# LPCB218_-_CORE_INTERFACE.net
KiCad netlist of a schematic drawn in Altium Designer
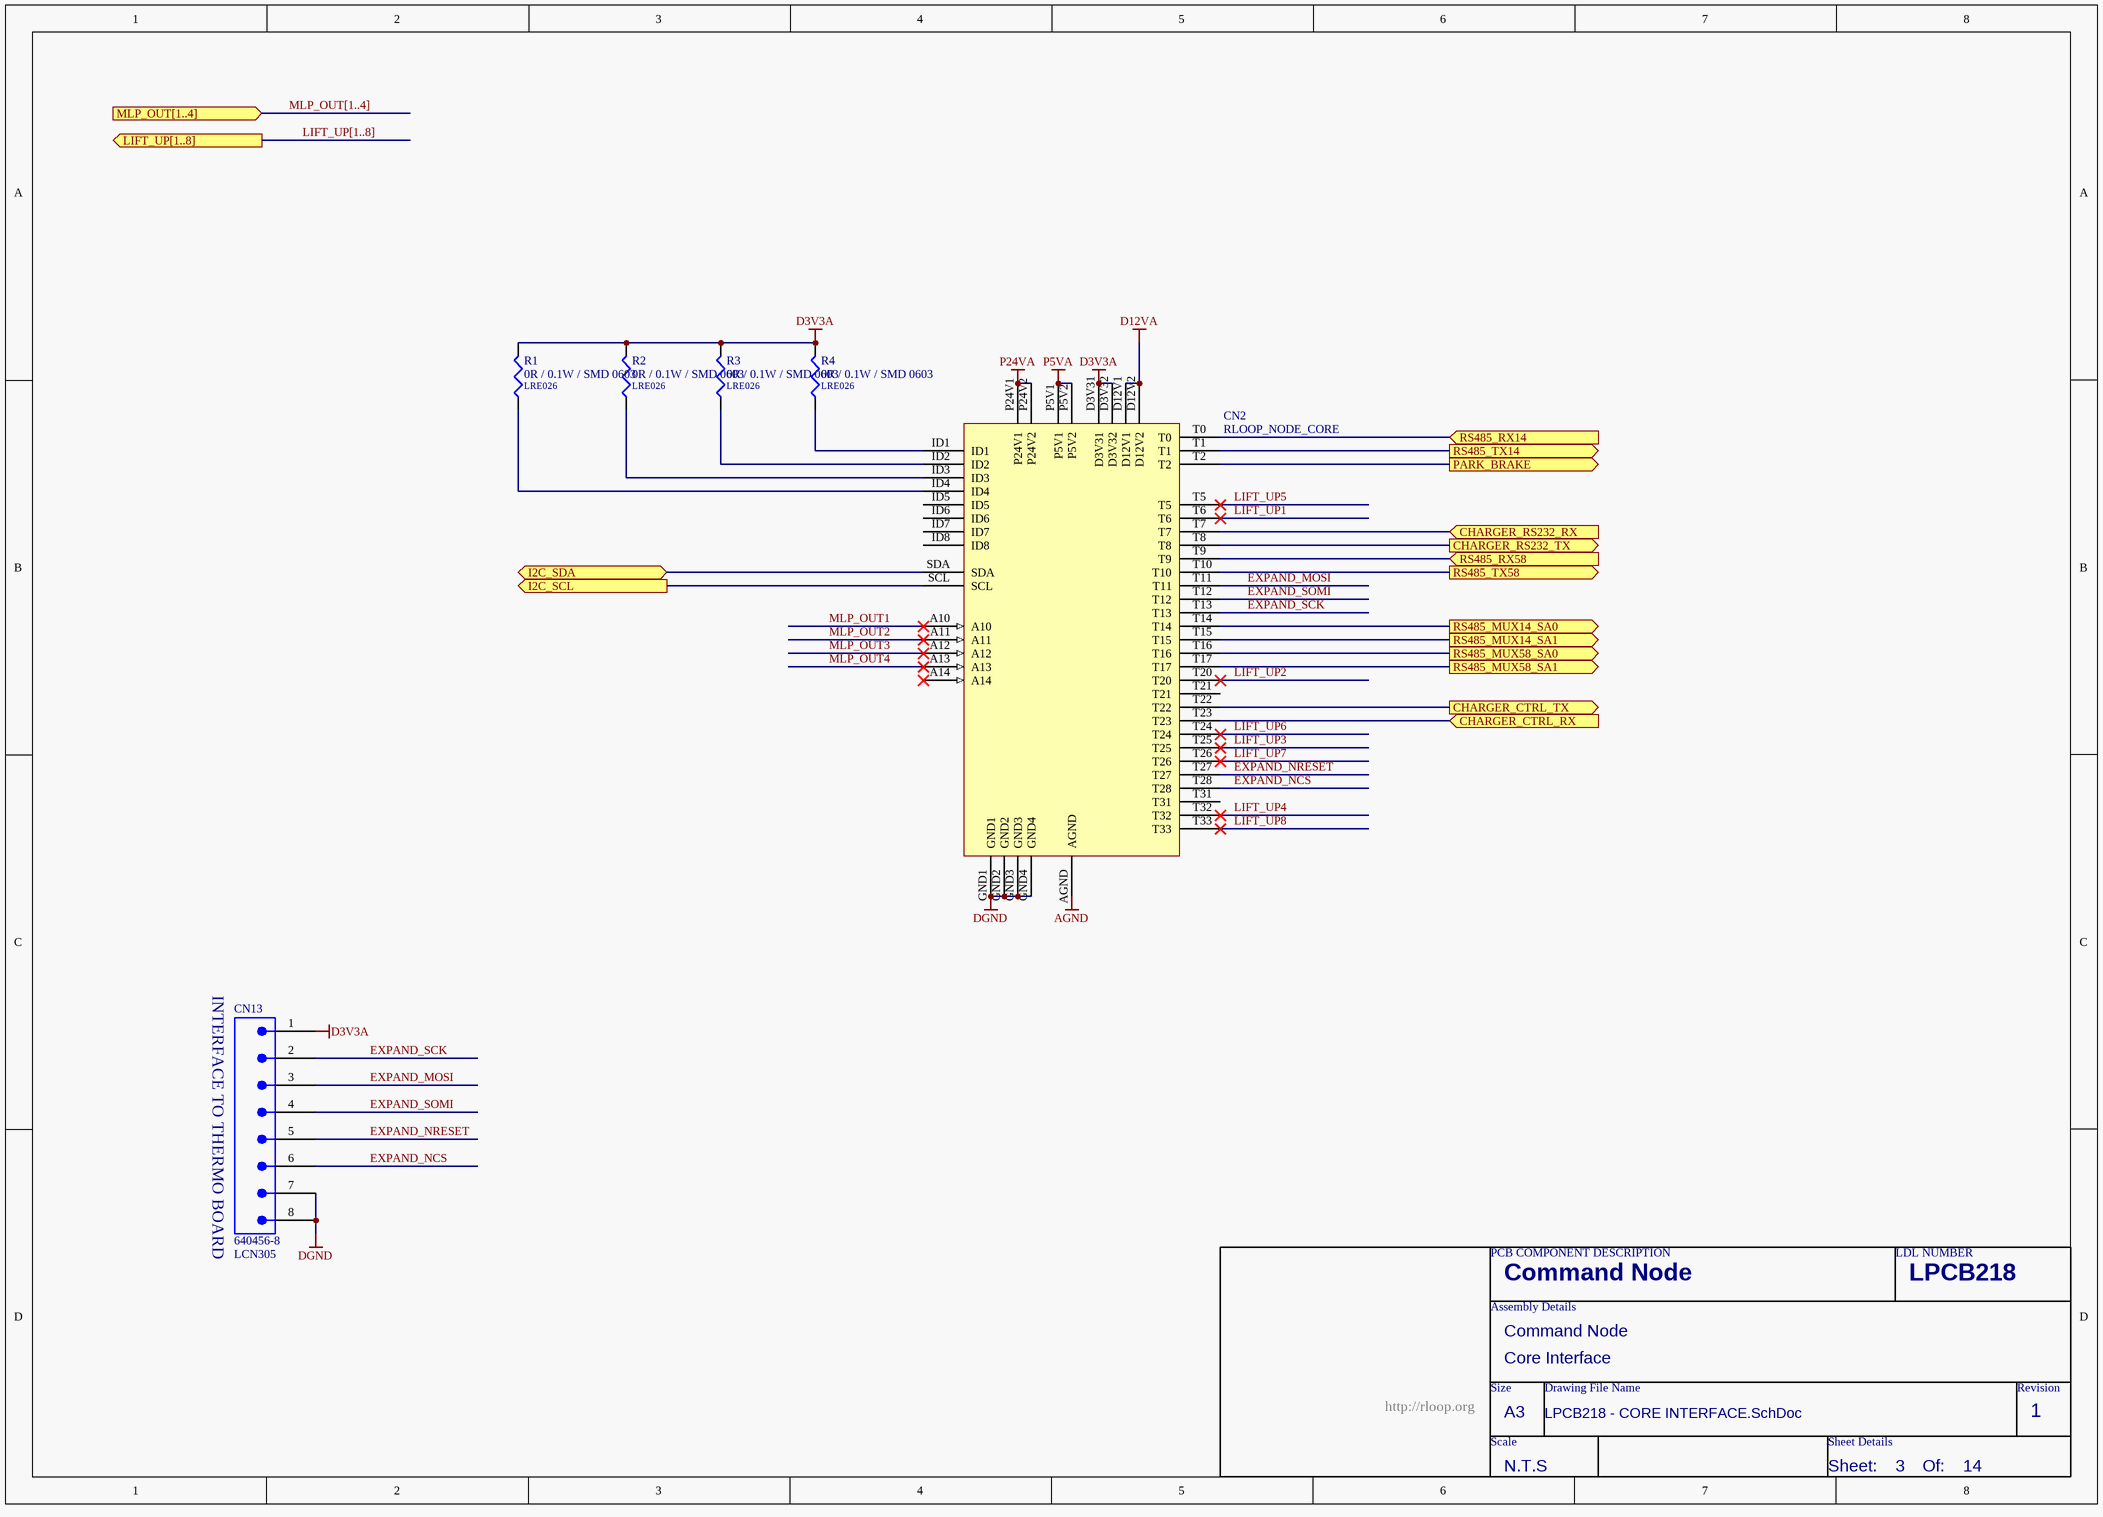
[diagram p0: LPCB218 - CORE INTERFACE.SchDoc]

(export (version "E")
  (design (tool "Eeschema 10.0.6"))
  (components
    (comp (ref "CN2")
      (value "RLOOP_NODE_CORE")
      (footprint "RLOOP_NODE_CORE")
      (description "rLoop Node Core Connector")
      (libsource (lib "LDL_Connectors") (part "RLOOP_NODE_CORE"))
    )
    (comp (ref "CN13")
      (value "640456-8")
      (footprint "640456-8")
      (description "Connector, Male Header, 8 Way")
      (fields (field (name "LDL_NUMBER") "LCN305"))
      (libsource (lib "LDL_Connectors") (part "640456-8"))
    )
    (comp (ref "R1")
      (value "0R / 0.1W / SMD 0603")
      (footprint "LFP020__CR1608-0603-IPC7351_B")
      (description "Resistor, Ceramic Chip, 0R, 0.1W, SMD 0603 [LRE026]")
      (fields (field (name "LDL_NUMBER") "LRE026"))
      (libsource (lib "LDL_Resistors") (part "0R / 0.1W / SMD 0603"))
    )
    (comp (ref "R2")
      (value "0R / 0.1W / SMD 0603")
      (footprint "LFP020__CR1608-0603-IPC7351_B")
      (description "Resistor, Ceramic Chip, 0R, 0.1W, SMD 0603 [LRE026]")
      (fields (field (name "LDL_NUMBER") "LRE026"))
      (libsource (lib "LDL_Resistors") (part "0R / 0.1W / SMD 0603"))
    )
    (comp (ref "R3")
      (value "0R / 0.1W / SMD 0603")
      (footprint "LFP020__CR1608-0603-IPC7351_B")
      (description "Resistor, Ceramic Chip, 0R, 0.1W, SMD 0603 [LRE026]")
      (fields (field (name "LDL_NUMBER") "LRE026"))
      (libsource (lib "LDL_Resistors") (part "0R / 0.1W / SMD 0603"))
    )
    (comp (ref "R4")
      (value "0R / 0.1W / SMD 0603")
      (footprint "LFP020__CR1608-0603-IPC7351_B")
      (description "Resistor, Ceramic Chip, 0R, 0.1W, SMD 0603 [LRE026]")
      (fields (field (name "LDL_NUMBER") "LRE026"))
      (libsource (lib "LDL_Resistors") (part "0R / 0.1W / SMD 0603"))
    )
  )
  (nets
    (net (code "1") (name "/CHARGER_CTRL_RX") (class "Default")
      (node (ref "CN2") (pin "T23") (pinfunction "T23_T23") (pintype "passive"))
    )
    (net (code "2") (name "/CHARGER_CTRL_TX") (class "Default")
      (node (ref "CN2") (pin "T22") (pinfunction "T22_T22") (pintype "passive"))
    )
    (net (code "3") (name "/CHARGER_RS232_RX") (class "Default")
      (node (ref "CN2") (pin "T7") (pinfunction "T7_T7") (pintype "passive"))
    )
    (net (code "4") (name "/CHARGER_RS232_TX") (class "Default")
      (node (ref "CN2") (pin "T8") (pinfunction "T8_T8") (pintype "passive"))
    )
    (net (code "5") (name "/EXPAND_MOSI") (class "Default")
      (node (ref "CN13") (pin "3") (pinfunction "3_3") (pintype "passive"))
      (node (ref "CN2") (pin "T11") (pinfunction "T11_T11") (pintype "passive"))
    )
    (net (code "6") (name "/EXPAND_NCS") (class "Default")
      (node (ref "CN13") (pin "6") (pinfunction "6_6") (pintype "passive"))
      (node (ref "CN2") (pin "T28") (pinfunction "T28_T28") (pintype "passive"))
    )
    (net (code "7") (name "/EXPAND_NRESET") (class "Default")
      (node (ref "CN13") (pin "5") (pinfunction "5_5") (pintype "passive"))
      (node (ref "CN2") (pin "T27") (pinfunction "T27_T27") (pintype "passive"))
    )
    (net (code "8") (name "/EXPAND_SCK") (class "Default")
      (node (ref "CN13") (pin "2") (pinfunction "2_2") (pintype "passive"))
      (node (ref "CN2") (pin "T13") (pinfunction "T13_T13") (pintype "passive"))
    )
    (net (code "9") (name "/EXPAND_SOMI") (class "Default")
      (node (ref "CN13") (pin "4") (pinfunction "4_4") (pintype "passive"))
      (node (ref "CN2") (pin "T12") (pinfunction "T12_T12") (pintype "passive"))
    )
    (net (code "10") (name "/I2C_SCL") (class "Default")
      (node (ref "CN2") (pin "SCL") (pinfunction "SCL_SCL") (pintype "passive"))
    )
    (net (code "11") (name "/I2C_SDA") (class "Default")
      (node (ref "CN2") (pin "SDA") (pinfunction "SDA_SDA") (pintype "passive"))
    )
    (net (code "12") (name "/LIFT_UP1") (class "Default")
      (node (ref "CN2") (pin "T6") (pinfunction "T6_T6") (pintype "passive+no_connect"))
    )
    (net (code "13") (name "/LIFT_UP2") (class "Default")
      (node (ref "CN2") (pin "T20") (pinfunction "T20_T20") (pintype "passive+no_connect"))
    )
    (net (code "14") (name "/LIFT_UP3") (class "Default")
      (node (ref "CN2") (pin "T25") (pinfunction "T25_T25") (pintype "passive+no_connect"))
    )
    (net (code "15") (name "/LIFT_UP4") (class "Default")
      (node (ref "CN2") (pin "T32") (pinfunction "T32_T32") (pintype "passive+no_connect"))
    )
    (net (code "16") (name "/LIFT_UP5") (class "Default")
      (node (ref "CN2") (pin "T5") (pinfunction "T5_T5") (pintype "passive+no_connect"))
    )
    (net (code "17") (name "/LIFT_UP6") (class "Default")
      (node (ref "CN2") (pin "T24") (pinfunction "T24_T24") (pintype "passive+no_connect"))
    )
    (net (code "18") (name "/LIFT_UP7") (class "Default")
      (node (ref "CN2") (pin "T26") (pinfunction "T26_T26") (pintype "passive+no_connect"))
    )
    (net (code "19") (name "/LIFT_UP8") (class "Default")
      (node (ref "CN2") (pin "T33") (pinfunction "T33_T33") (pintype "passive+no_connect"))
    )
    (net (code "21") (name "/MLP_OUT1") (class "Default")
      (node (ref "CN2") (pin "A10") (pinfunction "A10_A10") (pintype "input+no_connect"))
    )
    (net (code "22") (name "/MLP_OUT2") (class "Default")
      (node (ref "CN2") (pin "A11") (pinfunction "A11_A11") (pintype "input+no_connect"))
    )
    (net (code "23") (name "/MLP_OUT3") (class "Default")
      (node (ref "CN2") (pin "A12") (pinfunction "A12_A12") (pintype "input+no_connect"))
    )
    (net (code "24") (name "/MLP_OUT4") (class "Default")
      (node (ref "CN2") (pin "A13") (pinfunction "A13_A13") (pintype "input+no_connect"))
    )
    (net (code "26") (name "/PARK_BRAKE") (class "Default")
      (node (ref "CN2") (pin "T2") (pinfunction "T2_T2") (pintype "passive"))
    )
    (net (code "27") (name "/RS485_MUX14_SA0") (class "Default")
      (node (ref "CN2") (pin "T14") (pinfunction "T14_T14") (pintype "passive"))
    )
    (net (code "28") (name "/RS485_MUX14_SA1") (class "Default")
      (node (ref "CN2") (pin "T15") (pinfunction "T15_T15") (pintype "passive"))
    )
    (net (code "29") (name "/RS485_MUX58_SA0") (class "Default")
      (node (ref "CN2") (pin "T16") (pinfunction "T16_T16") (pintype "passive"))
    )
    (net (code "30") (name "/RS485_MUX58_SA1") (class "Default")
      (node (ref "CN2") (pin "T17") (pinfunction "T17_T17") (pintype "passive"))
    )
    (net (code "31") (name "/RS485_RX14") (class "Default")
      (node (ref "CN2") (pin "T0") (pinfunction "T0_T0") (pintype "passive"))
    )
    (net (code "32") (name "/RS485_RX58") (class "Default")
      (node (ref "CN2") (pin "T9") (pinfunction "T9_T9") (pintype "passive"))
    )
    (net (code "33") (name "/RS485_TX14") (class "Default")
      (node (ref "CN2") (pin "T1") (pinfunction "T1_T1") (pintype "passive"))
    )
    (net (code "34") (name "/RS485_TX58") (class "Default")
      (node (ref "CN2") (pin "T10") (pinfunction "T10_T10") (pintype "passive"))
    )
    (net (code "35") (name "AGND") (class "Default")
      (node (ref "CN2") (pin "AGND") (pinfunction "AGND_AGND") (pintype "power_in"))
    )
    (net (code "36") (name "D3V3A") (class "Default")
      (node (ref "CN13") (pin "1") (pinfunction "1_1") (pintype "passive"))
      (node (ref "CN2") (pin "D3V31") (pinfunction "D3V31_D3V31") (pintype "power_in"))
      (node (ref "CN2") (pin "D3V32") (pinfunction "D3V32_D3V32") (pintype "power_in"))
      (node (ref "R1") (pin "2") (pintype "passive"))
      (node (ref "R2") (pin "2") (pintype "passive"))
      (node (ref "R3") (pin "2") (pintype "passive"))
      (node (ref "R4") (pin "2") (pintype "passive"))
    )
    (net (code "37") (name "D12VA") (class "Default")
      (node (ref "CN2") (pin "D12V1") (pinfunction "D12V1_D12V1") (pintype "power_in"))
      (node (ref "CN2") (pin "D12V2") (pinfunction "D12V2_D12V2") (pintype "power_in"))
    )
    (net (code "38") (name "DGND") (class "Default")
      (node (ref "CN13") (pin "7") (pinfunction "7_7") (pintype "passive"))
      (node (ref "CN13") (pin "8") (pinfunction "8_8") (pintype "passive"))
      (node (ref "CN2") (pin "GND1") (pinfunction "GND1_GND1") (pintype "power_in"))
      (node (ref "CN2") (pin "GND2") (pinfunction "GND2_GND2") (pintype "power_in"))
      (node (ref "CN2") (pin "GND3") (pinfunction "GND3_GND3") (pintype "power_in"))
      (node (ref "CN2") (pin "GND4") (pinfunction "GND4_GND4") (pintype "power_in"))
    )
    (net (code "39") (name "Net-(CN2-PadID1)") (class "Default")
      (node (ref "CN2") (pin "ID1") (pinfunction "ID1_ID1") (pintype "passive"))
      (node (ref "R4") (pin "1") (pintype "passive"))
    )
    (net (code "40") (name "Net-(CN2-PadID2)") (class "Default")
      (node (ref "CN2") (pin "ID2") (pinfunction "ID2_ID2") (pintype "passive"))
      (node (ref "R3") (pin "1") (pintype "passive"))
    )
    (net (code "41") (name "Net-(CN2-PadID3)") (class "Default")
      (node (ref "CN2") (pin "ID3") (pinfunction "ID3_ID3") (pintype "passive"))
      (node (ref "R2") (pin "1") (pintype "passive"))
    )
    (net (code "42") (name "Net-(CN2-PadID4)") (class "Default")
      (node (ref "CN2") (pin "ID4") (pinfunction "ID4_ID4") (pintype "passive"))
      (node (ref "R1") (pin "1") (pintype "passive"))
    )
    (net (code "43") (name "P5VA") (class "Default")
      (node (ref "CN2") (pin "P5V1") (pinfunction "P5V1_P5V1") (pintype "power_in"))
      (node (ref "CN2") (pin "P5V2") (pinfunction "P5V2_P5V2") (pintype "power_in"))
    )
    (net (code "44") (name "P24VA") (class "Default")
      (node (ref "CN2") (pin "P24V1") (pinfunction "P24V1_P24V1") (pintype "power_in"))
      (node (ref "CN2") (pin "P24V2") (pinfunction "P24V2_P24V2") (pintype "power_in"))
    )
    (net (code "45") (name "unconnected-(CN2-PadA14)") (class "Default")
      (node (ref "CN2") (pin "A14") (pinfunction "A14_A14") (pintype "input+no_connect"))
    )
    (net (code "46") (name "unconnected-(CN2-PadID5)") (class "Default")
      (node (ref "CN2") (pin "ID5") (pinfunction "ID5_ID5") (pintype "passive"))
    )
    (net (code "47") (name "unconnected-(CN2-PadID6)") (class "Default")
      (node (ref "CN2") (pin "ID6") (pinfunction "ID6_ID6") (pintype "passive"))
    )
    (net (code "48") (name "unconnected-(CN2-PadID7)") (class "Default")
      (node (ref "CN2") (pin "ID7") (pinfunction "ID7_ID7") (pintype "passive"))
    )
    (net (code "49") (name "unconnected-(CN2-PadID8)") (class "Default")
      (node (ref "CN2") (pin "ID8") (pinfunction "ID8_ID8") (pintype "passive"))
    )
    (net (code "50") (name "unconnected-(CN2-PadT21)") (class "Default")
      (node (ref "CN2") (pin "T21") (pinfunction "T21_T21") (pintype "passive"))
    )
    (net (code "51") (name "unconnected-(CN2-PadT31)") (class "Default")
      (node (ref "CN2") (pin "T31") (pinfunction "T31_T31") (pintype "passive"))
    )
  )
)
